# SHT-BREAD.net
KiCad netlist of a schematic drawn in Altium Designer
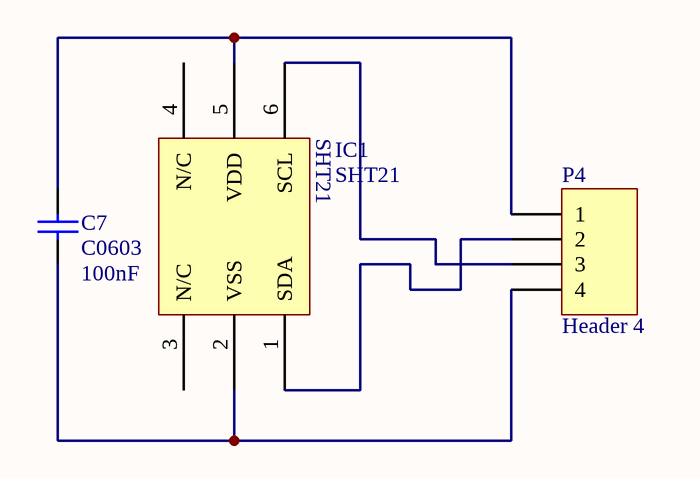
[diagram p0: SHT-BREAD.SchDoc]

(export (version "E")
  (design (tool "Eeschema 10.0.6"))
  (components
    (comp (ref "C7")
      (value "C0603")
      (footprint "0603")
      (description "Ceramic Chip Capacitor - Standard")
      (fields (field (name "ALTIUM_VALUE") "100nF") (field (name "PUBLISHER") "Altium Limited"))
      (libsource (lib "KEMET Chip Capacitor") (part "C0603"))
    )
    (comp (ref "IC1") (value "SHT21") (footprint "PCBComponent_1") (libsource (lib "SHT21") (part "SHT21")))
    (comp (ref "P4")
      (value "Header 4")
      (footprint "HDR1X4")
      (description "Header, 4-Pin")
      (fields (field (name "PUBLISHER") "Altium Limited"))
      (libsource (lib "Miscellaneous Connectors") (part "Header 4"))
    )
  )
  (nets
    (net (code "1") (name "Net-(IC1-SCL)") (class "Default")
      (node (ref "IC1") (pin "6") (pinfunction "SCL_6") (pintype "passive"))
      (node (ref "P4") (pin "3") (pinfunction "3_3") (pintype "passive"))
    )
    (net (code "2") (name "Net-(IC1-SDA)") (class "Default")
      (node (ref "IC1") (pin "1") (pinfunction "SDA_1") (pintype "passive"))
      (node (ref "P4") (pin "2") (pinfunction "2_2") (pintype "passive"))
    )
    (net (code "3") (name "Net-(IC1-VDD)") (class "Default")
      (node (ref "C7") (pin "1") (pinfunction "1_1") (pintype "passive"))
      (node (ref "IC1") (pin "5") (pinfunction "VDD_5") (pintype "passive"))
      (node (ref "P4") (pin "1") (pinfunction "1_1") (pintype "passive"))
    )
    (net (code "4") (name "Net-(IC1-VSS)") (class "Default")
      (node (ref "C7") (pin "2") (pinfunction "2_2") (pintype "passive"))
      (node (ref "IC1") (pin "2") (pinfunction "VSS_2") (pintype "passive"))
      (node (ref "P4") (pin "4") (pinfunction "4_4") (pintype "passive"))
    )
    (net (code "5") (name "unconnected-(IC1-N{slash}C-Pad3)") (class "Default")
      (node (ref "IC1") (pin "3") (pinfunction "N/C_3") (pintype "passive"))
    )
    (net (code "6") (name "unconnected-(IC1-N{slash}C-Pad4)") (class "Default")
      (node (ref "IC1") (pin "4") (pinfunction "N/C_4") (pintype "passive"))
    )
  )
)
